# DPPXHK_10CL010_DEBUGPORT.net
KiCad netlist of a schematic drawn in Altium Designer
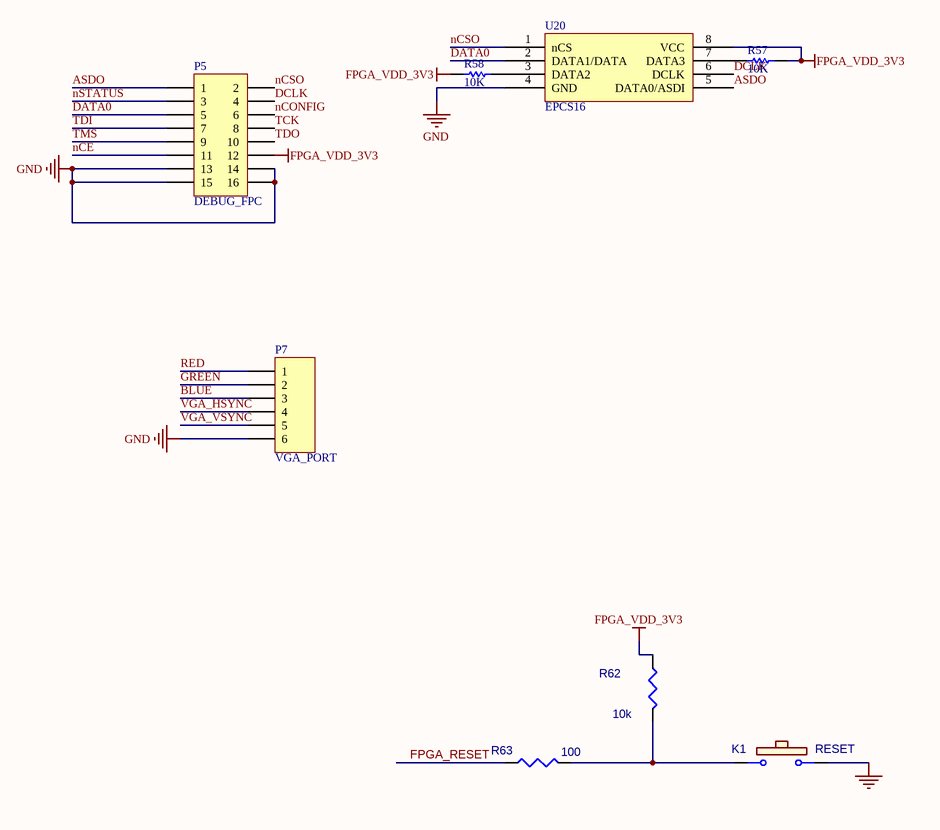
[diagram p0: DPPXHK_10CL010_DEBUGPORT.SchDoc]

(export (version "E")
  (design (tool "Eeschema 10.0.6"))
  (components
    (comp (ref "K1") (value "RESET") (libsource (lib "*") (part "KEYB")))
    (comp (ref "P5")
      (value "DEBUG_FPC")
      (footprint "FPC-0.5-16")
      (description "Header, 8-Pin, Dual row")
      (fields (field (name "PUBLISHER") "Altium Limited"))
      (libsource (lib "Miscellaneous Connectors") (part "Header 8X2"))
    )
    (comp (ref "P7")
      (value "VGA_PORT")
      (footprint "FPC-0.5-6")
      (description "Header, 6-Pin")
      (fields (field (name "PUBLISHER") "Altium Limited"))
      (libsource (lib "Miscellaneous Connectors") (part "Header 6"))
    )
    (comp (ref "R57")
      (value "10K")
      (footprint "0402R")
      (description "Resistor")
      (fields
        (field (name "MANUFACTURER") "Generic Components")
        (field (name "PUBLISHER") "Altium Hobart Technology Centre")
      )
      (libsource (lib "*") (part "Res1"))
    )
    (comp (ref "R58")
      (value "10K")
      (footprint "0402R")
      (description "Resistor")
      (fields
        (field (name "MANUFACTURER") "Generic Components")
        (field (name "PUBLISHER") "Altium Hobart Technology Centre")
      )
      (libsource (lib "*") (part "Res1"))
    )
    (comp (ref "R62") (value "10k") (footprint "0402R") (libsource (lib "*") (part "R_Dup2")))
    (comp (ref "R63") (value "100") (footprint "0402R") (libsource (lib "*") (part "R_Dup2")))
    (comp (ref "U20") (value "EPCS16") (footprint "SO-g8") (libsource (lib "PXHK") (part "EPCS16")))
  )
  (nets
    (net (code "1") (name "/ASDO") (class "Default")
      (node (ref "P5") (pin "1") (pinfunction "1_1") (pintype "passive"))
      (node (ref "U20") (pin "5") (pinfunction "DATA0/ASDI_5") (pintype "passive"))
    )
    (net (code "2") (name "/BLUE") (class "Default")
      (node (ref "P7") (pin "3") (pinfunction "3_3") (pintype "passive"))
    )
    (net (code "3") (name "/DATA0") (class "Default")
      (node (ref "P5") (pin "5") (pinfunction "5_5") (pintype "passive"))
      (node (ref "U20") (pin "2") (pinfunction "DATA1/DATA_2") (pintype "passive"))
    )
    (net (code "4") (name "/DCLK") (class "Default")
      (node (ref "P5") (pin "4") (pinfunction "4_4") (pintype "passive"))
      (node (ref "U20") (pin "6") (pinfunction "DCLK_6") (pintype "passive"))
    )
    (net (code "5") (name "/FPGA_RESET") (class "Default")
      (node (ref "R63") (pin "1") (pinfunction "1_1") (pintype "passive"))
    )
    (net (code "6") (name "/GREEN") (class "Default")
      (node (ref "P7") (pin "2") (pinfunction "2_2") (pintype "passive"))
    )
    (net (code "7") (name "/RED") (class "Default")
      (node (ref "P7") (pin "1") (pinfunction "1_1") (pintype "passive"))
    )
    (net (code "8") (name "/TCK") (class "Default")
      (node (ref "P5") (pin "8") (pinfunction "8_8") (pintype "passive"))
    )
    (net (code "9") (name "/TDI") (class "Default")
      (node (ref "P5") (pin "7") (pinfunction "7_7") (pintype "passive"))
    )
    (net (code "10") (name "/TDO") (class "Default")
      (node (ref "P5") (pin "10") (pinfunction "10_10") (pintype "passive"))
    )
    (net (code "11") (name "/TMS") (class "Default")
      (node (ref "P5") (pin "9") (pinfunction "9_9") (pintype "passive"))
    )
    (net (code "12") (name "/VGA_HSYNC") (class "Default")
      (node (ref "P7") (pin "4") (pinfunction "4_4") (pintype "passive"))
    )
    (net (code "13") (name "/VGA_VSYNC") (class "Default")
      (node (ref "P7") (pin "5") (pinfunction "5_5") (pintype "passive"))
    )
    (net (code "14") (name "/nCE") (class "Default")
      (node (ref "P5") (pin "11") (pinfunction "11_11") (pintype "passive"))
    )
    (net (code "15") (name "/nCONFIG") (class "Default")
      (node (ref "P5") (pin "6") (pinfunction "6_6") (pintype "passive"))
    )
    (net (code "16") (name "/nCSO") (class "Default")
      (node (ref "P5") (pin "2") (pinfunction "2_2") (pintype "passive"))
      (node (ref "U20") (pin "1") (pinfunction "nCS_1") (pintype "passive"))
    )
    (net (code "17") (name "/nSTATUS") (class "Default")
      (node (ref "P5") (pin "3") (pinfunction "3_3") (pintype "passive"))
    )
    (net (code "18") (name "FPGA_VDD_3V3") (class "Default")
      (node (ref "P5") (pin "12") (pinfunction "12_12") (pintype "passive"))
      (node (ref "R57") (pin "2") (pinfunction "2_2") (pintype "passive"))
      (node (ref "R58") (pin "1") (pinfunction "1_1") (pintype "passive"))
      (node (ref "R62") (pin "1") (pinfunction "1_1") (pintype "passive"))
      (node (ref "U20") (pin "8") (pinfunction "VCC_8") (pintype "passive"))
    )
    (net (code "19") (name "GND") (class "Default")
      (node (ref "K1") (pin "2") (pinfunction "2_2") (pintype "passive"))
      (node (ref "P5") (pin "13") (pinfunction "13_13") (pintype "passive"))
      (node (ref "P5") (pin "14") (pinfunction "14_14") (pintype "passive"))
      (node (ref "P5") (pin "15") (pinfunction "15_15") (pintype "passive"))
      (node (ref "P5") (pin "16") (pinfunction "16_16") (pintype "passive"))
      (node (ref "P7") (pin "6") (pinfunction "6_6") (pintype "passive"))
      (node (ref "U20") (pin "4") (pinfunction "GND_4") (pintype "passive"))
    )
    (net (code "20") (name "Net-(K1-Pad1)") (class "Default")
      (node (ref "K1") (pin "1") (pinfunction "1_1") (pintype "passive"))
      (node (ref "R62") (pin "2") (pinfunction "2_2") (pintype "passive"))
      (node (ref "R63") (pin "2") (pinfunction "2_2") (pintype "passive"))
    )
    (net (code "21") (name "Net-(U20-DATA2)") (class "Default")
      (node (ref "R58") (pin "2") (pinfunction "2_2") (pintype "passive"))
      (node (ref "U20") (pin "3") (pinfunction "DATA2_3") (pintype "passive"))
    )
    (net (code "22") (name "Net-(U20-DATA3)") (class "Default")
      (node (ref "R57") (pin "1") (pinfunction "1_1") (pintype "passive"))
      (node (ref "U20") (pin "7") (pinfunction "DATA3_7") (pintype "passive"))
    )
  )
)
